# cpu.net
KiCad netlist of a schematic drawn in Altium Designer
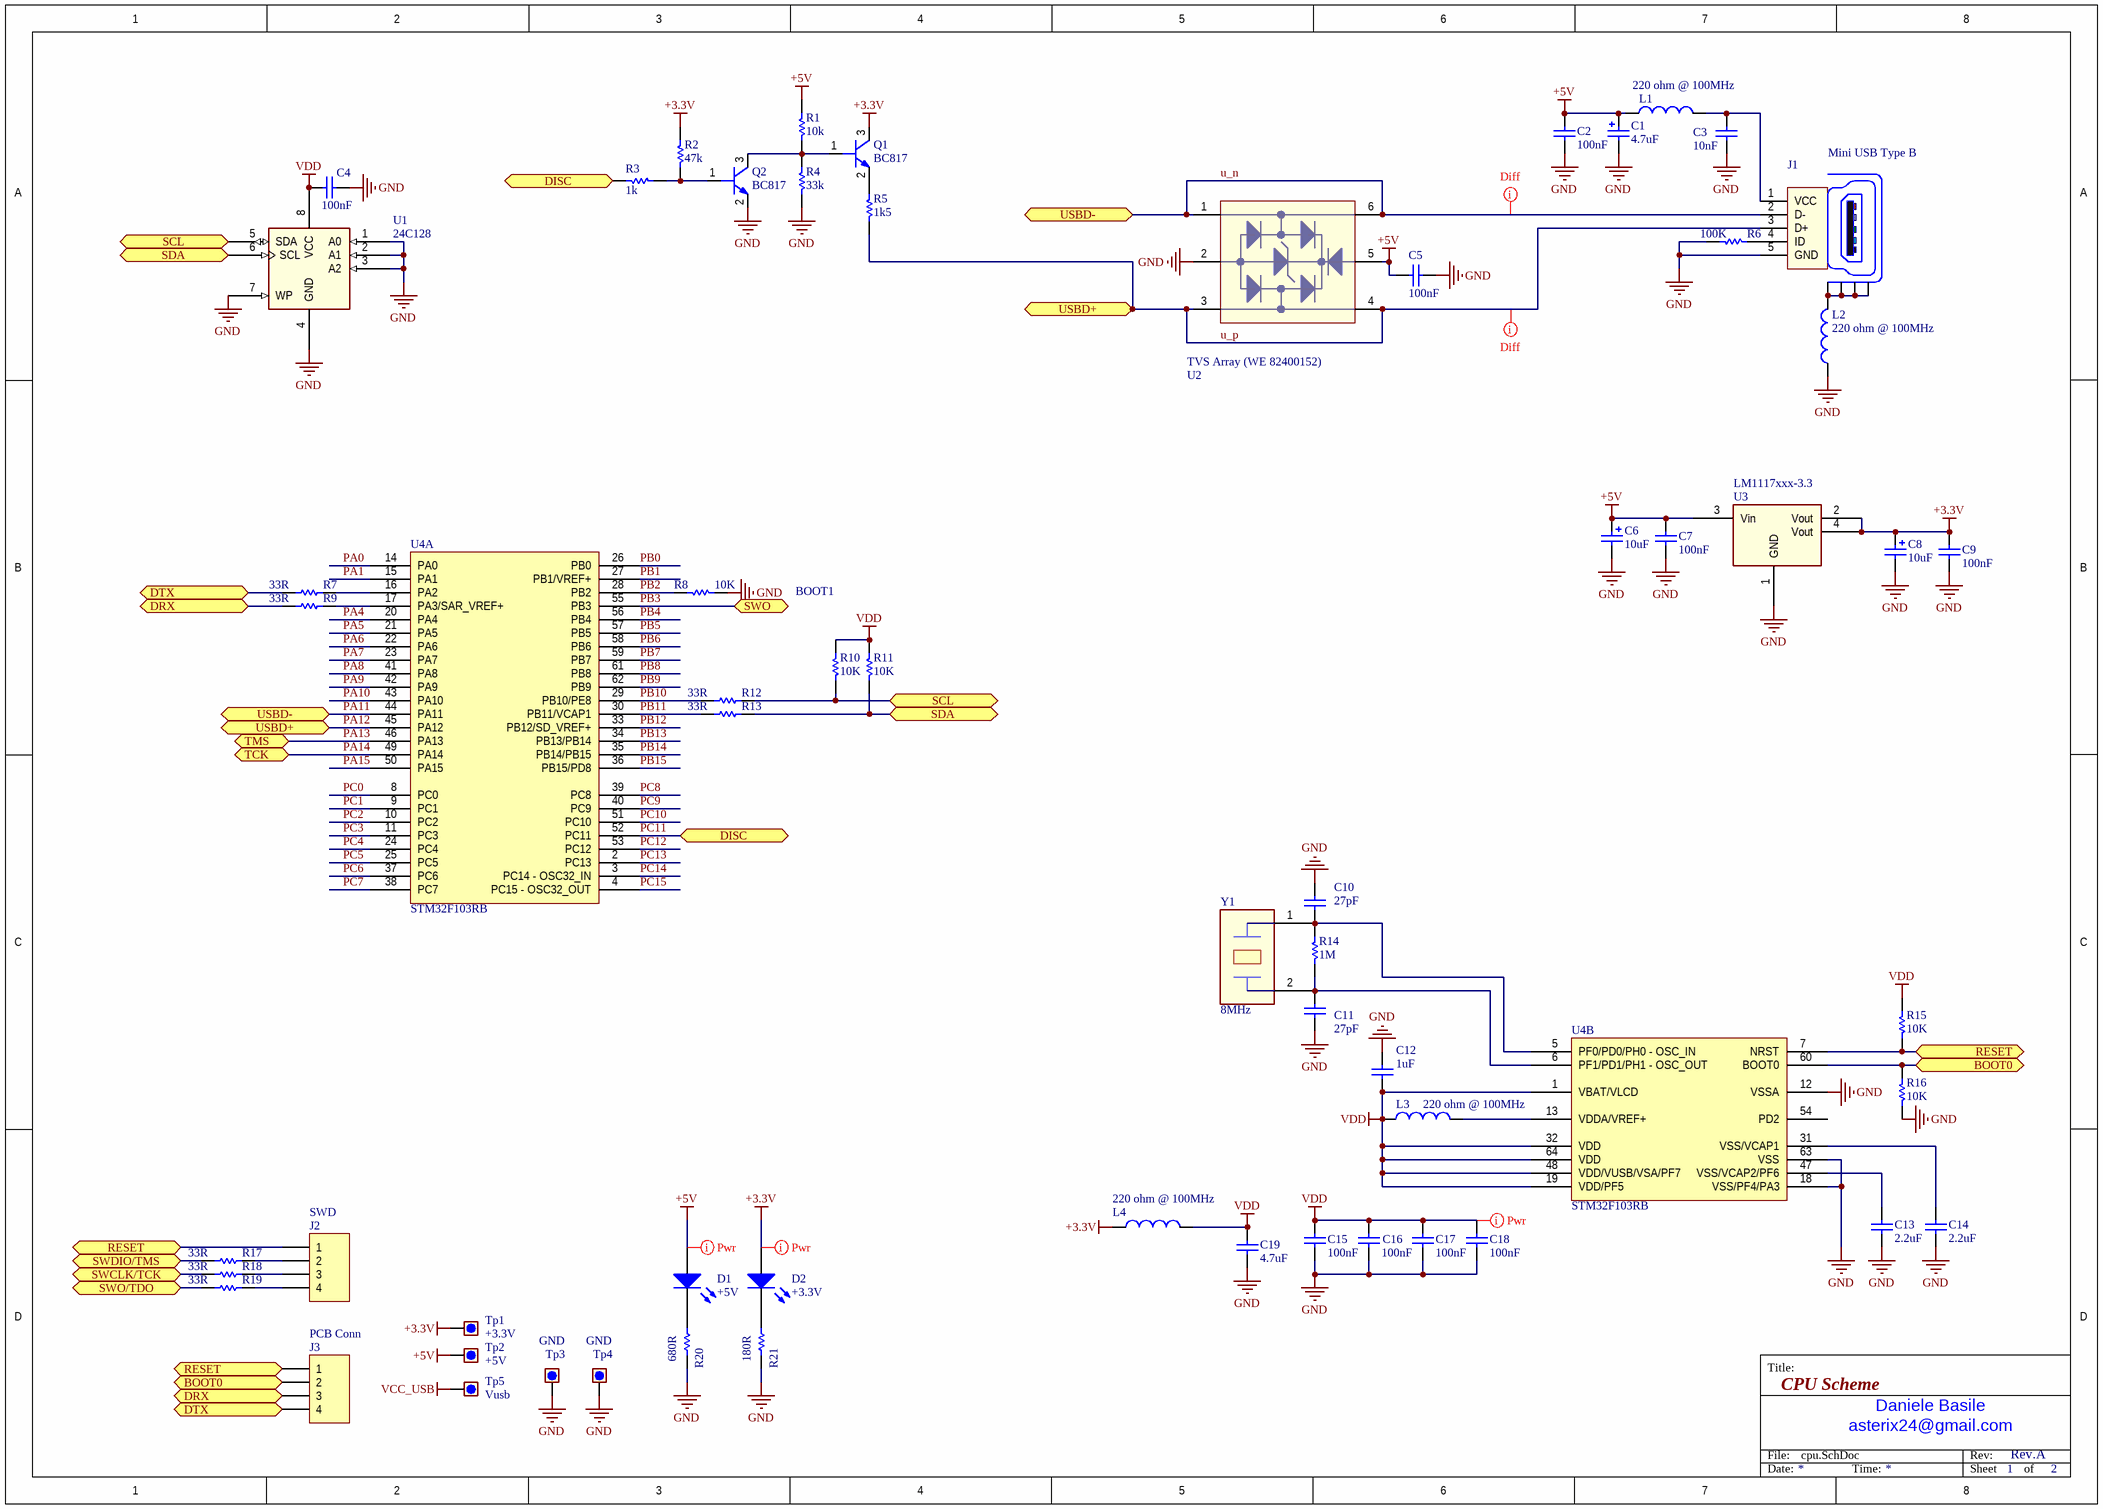
[diagram p0: cpu.SchDoc]

(export (version "E")
  (design (tool "Eeschema 10.0.6"))
  (components
    (comp (ref "C1")
      (value "4.7uF")
      (footprint "1206_[3216]")
      (description "Ceramic X7R 16V")
      (fields (field (name "PUBLISHER") "Altium Limited"))
      (libsource (lib "DEVELER_Library") (part "Cap Pol1"))
    )
    (comp (ref "C2")
      (value "100nF")
      (footprint "0603_[1608]")
      (description "Ceramic X7R 50V")
      (fields (field (name "PUBLISHER") "Altium Limited"))
      (libsource (lib "DEVELER_Library") (part "Cap"))
    )
    (comp (ref "C3")
      (value "10nF")
      (footprint "0603_[1608]")
      (description "Ceramic X7R 50V")
      (fields (field (name "PUBLISHER") "Altium Limited"))
      (libsource (lib "DEVELER_Library") (part "Cap"))
    )
    (comp (ref "C4")
      (value "100nF")
      (footprint "0603_[1608]")
      (description "Ceramic X7R 50V")
      (fields (field (name "PUBLISHER") "Altium Limited"))
      (libsource (lib "DEVELER_Library") (part "Cap"))
    )
    (comp (ref "C5")
      (value "100nF")
      (footprint "0603_[1608]")
      (description "Ceramic X7R 50V")
      (fields (field (name "PUBLISHER") "Altium Limited"))
      (libsource (lib "Miscellaneous Devices") (part "Cap"))
    )
    (comp (ref "C6")
      (value "10uF")
      (footprint "1206_[3216]")
      (description "Ceramic X5R 25V")
      (fields (field (name "PUBLISHER") "Altium Limited"))
      (libsource (lib "") (part "Cap Pol1_1"))
    )
    (comp (ref "C7")
      (value "100nF")
      (footprint "0603_[1608]")
      (description "Ceramic X7R 50V")
      (fields (field (name "PUBLISHER") "Altium Limited"))
      (libsource (lib "") (part "Cap_1"))
    )
    (comp (ref "C8")
      (value "10uF")
      (footprint "1206_[3216]")
      (description "Ceramic X5R 25V")
      (fields (field (name "PUBLISHER") "Altium Limited"))
      (libsource (lib "") (part "Cap Pol1_1"))
    )
    (comp (ref "C9")
      (value "100nF")
      (footprint "0603_[1608]")
      (description "Ceramic X7R 50V")
      (fields (field (name "PUBLISHER") "Altium Limited"))
      (libsource (lib "") (part "Cap_1"))
    )
    (comp (ref "C10")
      (value "27pF")
      (footprint "0603_[1608]")
      (description "Ceramic NP0 +/- 0.1")
      (fields (field (name "PUBLISHER") "Altium Limited"))
      (libsource (lib "simboli") (part "Cap"))
    )
    (comp (ref "C11")
      (value "27pF")
      (footprint "0603_[1608]")
      (description "Ceramic NP0 +/- 0.1")
      (fields (field (name "PUBLISHER") "Altium Limited"))
      (libsource (lib "simboli") (part "Cap"))
    )
    (comp (ref "C12")
      (value "1uF")
      (footprint "0603_[1608]")
      (description "Ceramic X7R 16V")
      (fields (field (name "PUBLISHER") "Altium Limited"))
      (libsource (lib "Miscellaneous Devices") (part "Cap"))
    )
    (comp (ref "C13")
      (value "2.2uF")
      (footprint "0603_[1608]")
      (description "Ceramic 6.3V X7R")
      (fields (field (name "PUBLISHER") "Altium Limited"))
      (libsource (lib "Miscellaneous Devices") (part "Cap"))
    )
    (comp (ref "C14")
      (value "2.2uF")
      (footprint "0603_[1608]")
      (description "Ceramic 6.3V X7R")
      (fields (field (name "PUBLISHER") "Altium Limited"))
      (libsource (lib "Miscellaneous Devices") (part "Cap"))
    )
    (comp (ref "C15")
      (value "100nF")
      (footprint "0603_[1608]")
      (description "Ceramic X7R 50V")
      (fields (field (name "PUBLISHER") "Altium Limited"))
      (libsource (lib "Miscellaneous Devices") (part "Cap"))
    )
    (comp (ref "C16")
      (value "100nF")
      (footprint "0603_[1608]")
      (description "Ceramic X7R 50V")
      (fields (field (name "PUBLISHER") "Altium Limited"))
      (libsource (lib "Miscellaneous Devices") (part "Cap"))
    )
    (comp (ref "C17")
      (value "100nF")
      (footprint "0603_[1608]")
      (description "Ceramic X7R 50V")
      (fields (field (name "PUBLISHER") "Altium Limited"))
      (libsource (lib "Miscellaneous Devices") (part "Cap"))
    )
    (comp (ref "C18")
      (value "100nF")
      (footprint "0603_[1608]")
      (description "Ceramic X7R 50V")
      (fields (field (name "PUBLISHER") "Altium Limited"))
      (libsource (lib "Miscellaneous Devices") (part "Cap"))
    )
    (comp (ref "C19")
      (value "4.7uF")
      (footprint "0603_[1608]")
      (description "Ceramic X7R 16V")
      (fields (field (name "PUBLISHER") "Altium Limited"))
      (libsource (lib "simboli") (part "Cap"))
    )
    (comp (ref "D1")
      (value "+5V")
      (footprint "0603_[1608]_LED")
      (description "LED Green")
      (fields (field (name "PUBLISHER") "Altium Limited"))
      (libsource (lib "DEVELER_Library") (part "LED0"))
    )
    (comp (ref "D2")
      (value "+3.3V")
      (footprint "0603_[1608]_LED")
      (description "LED Green")
      (fields (field (name "PUBLISHER") "Altium Limited"))
      (libsource (lib "DEVELER_Library") (part "LED0"))
    )
    (comp (ref "J1")
      (value "Mini USB Type B")
      (footprint "usb_typeB_mini_smd")
      (description "Mini USB SMT Type B 5 Contacts")
      (fields
        (field (name "MANUFACTURER") "Würth Elektronik eiSos GmbH")
        (field (name "PARTNO") "65100516121")
        (field (name "CREATED BY") "Karrer Zheng")
      )
      (libsource (lib "develer_library") (part "USB_Con_Type_B_mini_SMT"))
    )
    (comp (ref "J2")
      (value "SWD")
      (footprint "HEADER_1X4_2.54MM_THD")
      (description "Pin Header, 1x4, 2.54mm.")
      (fields (field (name "PUBLISHER") "Altium Limited"))
      (libsource (lib "Miscellaneous Connectors") (part "Header 4"))
    )
    (comp (ref "J3")
      (value "PCB Conn")
      (footprint "HEADER_1X4_2.54MM_THD")
      (description "Pin Header, 1x4, 2.54mm.")
      (fields (field (name "PUBLISHER") "Altium Limited"))
      (libsource (lib "Miscellaneous Connectors") (part "Header 4"))
    )
    (comp (ref "L1")
      (value "220 ohm @ 100MHz")
      (footprint "0805_[2012]")
      (description "WE 742792022")
      (libsource (lib "DEVELER_Library") (part "Inductor"))
    )
    (comp (ref "L2")
      (value "220 ohm @ 100MHz")
      (footprint "0805_[2012]")
      (description "WE 742792022")
      (libsource (lib "DEVELER_Library") (part "Inductor"))
    )
    (comp (ref "L3")
      (value "220 ohm @ 100MHz")
      (footprint "0805_[2012]")
      (description "Inductor")
      (fields (field (name "PUBLISHER") "Altium Limited"))
      (libsource (lib "Miscellaneous Devices") (part "Inductor"))
    )
    (comp (ref "L4")
      (value "220 ohm @ 100MHz")
      (footprint "0805_[2012]")
      (description "WE 742792022")
      (libsource (lib "DEVELER_Library") (part "Inductor"))
    )
    (comp (ref "Q1")
      (value "BC817")
      (footprint "SOT-23")
      (description "BJT NPN")
      (libsource (lib "develer_library") (part "BC817"))
    )
    (comp (ref "Q2")
      (value "BC817")
      (footprint "SOT-23")
      (description "BJT NPN")
      (libsource (lib "develer_library") (part "BC817"))
    )
    (comp (ref "R1")
      (value "10k")
      (footprint "0603_[1608]")
      (description "Resistor")
      (fields (field (name "PUBLISHER") "Altium Limited"))
      (libsource (lib "") (part "Res1_1"))
    )
    (comp (ref "R2")
      (value "47k")
      (footprint "0603_[1608]")
      (description "Resistor")
      (fields (field (name "PUBLISHER") "Altium Limited"))
      (libsource (lib "") (part "Res1_1"))
    )
    (comp (ref "R3")
      (value "1k")
      (footprint "0603_[1608]")
      (description "Resistor")
      (fields (field (name "PUBLISHER") "Altium Limited"))
      (libsource (lib "") (part "Res1_1"))
    )
    (comp (ref "R4")
      (value "33k")
      (footprint "0603_[1608]")
      (description "Resistor")
      (fields (field (name "PUBLISHER") "Altium Limited"))
      (libsource (lib "") (part "Res1_1"))
    )
    (comp (ref "R5")
      (value "1k5")
      (footprint "0603_[1608]")
      (description "Resistor")
      (fields (field (name "PUBLISHER") "Altium Limited"))
      (libsource (lib "") (part "Res1_1"))
    )
    (comp (ref "R6")
      (value "100K")
      (footprint "0603_[1608]")
      (description "Resistor")
      (libsource (lib "Miscellaneous Devices") (part "Res1"))
    )
    (comp (ref "R7")
      (value "33R")
      (footprint "0603_[1608]")
      (description "Resistor")
      (fields (field (name "PUBLISHER") "Altium Limited"))
      (libsource (lib "simboli") (part "Res1"))
    )
    (comp (ref "R8")
      (value "10K")
      (footprint "0603_[1608]")
      (description "Resistor")
      (fields (field (name "PUBLISHER") "Altium Limited"))
      (libsource (lib "simboli") (part "Res1"))
    )
    (comp (ref "R9")
      (value "33R")
      (footprint "0603_[1608]")
      (description "Resistor")
      (fields (field (name "PUBLISHER") "Altium Limited"))
      (libsource (lib "simboli") (part "Res1"))
    )
    (comp (ref "R10")
      (value "10K")
      (footprint "0603_[1608]")
      (description "Resistor")
      (fields (field (name "PUBLISHER") "Altium Limited"))
      (libsource (lib "") (part "Res1_1"))
    )
    (comp (ref "R11")
      (value "10K")
      (footprint "0603_[1608]")
      (description "Resistor")
      (fields (field (name "PUBLISHER") "Altium Limited"))
      (libsource (lib "") (part "Res1_1"))
    )
    (comp (ref "R12")
      (value "33R")
      (footprint "0603_[1608]")
      (description "Resistor")
      (fields (field (name "PUBLISHER") "Altium Limited"))
      (libsource (lib "simboli") (part "Res1"))
    )
    (comp (ref "R13")
      (value "33R")
      (footprint "0603_[1608]")
      (description "Resistor")
      (fields (field (name "PUBLISHER") "Altium Limited"))
      (libsource (lib "simboli") (part "Res1"))
    )
    (comp (ref "R14")
      (value "1M")
      (footprint "0603_[1608]")
      (description "Resistor")
      (fields (field (name "PUBLISHER") "Altium Limited"))
      (libsource (lib "") (part "Res1_1"))
    )
    (comp (ref "R15")
      (value "10K")
      (footprint "0603_[1608]")
      (description "Resistor")
      (fields (field (name "PUBLISHER") "Altium Limited"))
      (libsource (lib "simboli") (part "Res1"))
    )
    (comp (ref "R16")
      (value "10K")
      (footprint "0603_[1608]")
      (description "Resistor")
      (fields (field (name "PUBLISHER") "Altium Limited"))
      (libsource (lib "simboli") (part "Res1"))
    )
    (comp (ref "R17")
      (value "33R")
      (footprint "0603_[1608]")
      (description "Resistor")
      (fields (field (name "PUBLISHER") "Altium Limited"))
      (libsource (lib "simboli") (part "Res1"))
    )
    (comp (ref "R18")
      (value "33R")
      (footprint "0603_[1608]")
      (description "Resistor")
      (fields (field (name "PUBLISHER") "Altium Limited"))
      (libsource (lib "simboli") (part "Res1"))
    )
    (comp (ref "R19")
      (value "33R")
      (footprint "0603_[1608]")
      (description "Resistor")
      (fields (field (name "PUBLISHER") "Altium Limited"))
      (libsource (lib "simboli") (part "Res1"))
    )
    (comp (ref "R20")
      (value "680R")
      (footprint "0603_[1608]")
      (description "Resistor")
      (libsource (lib "DEVELER_Library") (part "Res1"))
    )
    (comp (ref "R21")
      (value "180R")
      (footprint "0603_[1608]")
      (description "Resistor")
      (libsource (lib "DEVELER_Library") (part "Res1"))
    )
    (comp (ref "Tp1")
      (value "+3.3V")
      (footprint "TEST_POINT_THD_D1.8MM")
      (description "Test point")
      (libsource (lib "DEVELER_Library") (part "Test_point"))
    )
    (comp (ref "Tp2")
      (value "+5V")
      (footprint "TEST_POINT_THD_D1.8MM")
      (description "Test point")
      (libsource (lib "DEVELER_Library") (part "Test_point"))
    )
    (comp (ref "Tp3")
      (value "GND")
      (footprint "TEST_POINT_THD_D1.8MM")
      (description "Test point")
      (libsource (lib "") (part "Test_point_1"))
    )
    (comp (ref "Tp4")
      (value "GND")
      (footprint "TEST_POINT_THD_D1.8MM")
      (description "Test point")
      (libsource (lib "") (part "Test_point_1"))
    )
    (comp (ref "Tp5")
      (value "Vusb")
      (footprint "TEST_POINT_THD_D1.8MM")
      (description "Test point")
      (libsource (lib "DEVELER_Library") (part "Test_point"))
    )
    (comp (ref "U1")
      (value "24C128")
      (footprint "SOIC8")
      (description "EEPROM")
      (libsource (lib "DEVELER_Library") (part "EEPROM-SOIC8"))
    )
    (comp (ref "U2")
      (value "TVS Array (WE 82400152)")
      (footprint "SOT-563")
      (libsource (lib "DEVELER_Library") (part "TVS_Diode_Array"))
    )
    (comp (ref "U3")
      (value "LM1117xxx-3.3")
      (footprint "SOT-223")
      (description "LM1117 LDO Fixed output")
      (libsource (lib "develer_library") (part "LM1117-FIXED-OUT"))
    )
    (comp (ref "U4")
      (value "STM32F103RB")
      (footprint "TSQFP50P1200X1200X160-64N")
      (libsource (lib "develer_library") (part "STM32F103RB"))
    )
    (comp (ref "Y1")
      (value "8MHz")
      (footprint "CRYSTAL_HC49UP")
      (libsource (lib "develer_library") (part "CRYSTAL-2p"))
    )
  )
  (nets
    (net (code "1") (name "+3.3V") (class "Default")
      (node (ref "C8") (pin "1") (pinfunction "1_1") (pintype "passive"))
      (node (ref "C9") (pin "2") (pinfunction "2_2") (pintype "passive"))
      (node (ref "D2") (pin "1") (pinfunction "A_1") (pintype "passive"))
      (node (ref "L4") (pin "1") (pinfunction "1_1") (pintype "passive"))
      (node (ref "Q1") (pin "3") (pinfunction "C_3") (pintype "passive"))
      (node (ref "R2") (pin "1") (pinfunction "1_1") (pintype "passive"))
      (node (ref "Tp1") (pin "1") (pinfunction "1_1") (pintype "passive"))
      (node (ref "U3") (pin "2") (pinfunction "Vout_2") (pintype "passive"))
      (node (ref "U3") (pin "4") (pinfunction "Vout_4") (pintype "passive"))
    )
    (net (code "2") (name "+5V") (class "Default")
      (node (ref "C1") (pin "1") (pinfunction "1_1") (pintype "passive"))
      (node (ref "C2") (pin "1") (pinfunction "1_1") (pintype "passive"))
      (node (ref "C5") (pin "2") (pinfunction "2_2") (pintype "passive"))
      (node (ref "C6") (pin "1") (pinfunction "1_1") (pintype "passive"))
      (node (ref "C7") (pin "2") (pinfunction "2_2") (pintype "passive"))
      (node (ref "D1") (pin "1") (pinfunction "A_1") (pintype "passive"))
      (node (ref "L1") (pin "1") (pinfunction "1_1") (pintype "passive"))
      (node (ref "R1") (pin "1") (pinfunction "1_1") (pintype "passive"))
      (node (ref "Tp2") (pin "1") (pinfunction "1_1") (pintype "passive"))
      (node (ref "U2") (pin "5") (pinfunction "5_5") (pintype "passive"))
      (node (ref "U3") (pin "3") (pinfunction "Vin_3") (pintype "passive"))
    )
    (net (code "3") (name "/BOOT0") (class "Default")
      (node (ref "J3") (pin "2") (pinfunction "2_2") (pintype "passive"))
      (node (ref "R16") (pin "2") (pinfunction "2_2") (pintype "passive"))
      (node (ref "U4") (pin "60") (pinfunction "BOOT0_60") (pintype "passive"))
    )
    (net (code "4") (name "/DRX") (class "Default")
      (node (ref "J3") (pin "3") (pinfunction "3_3") (pintype "passive"))
      (node (ref "R9") (pin "2") (pinfunction "2_2") (pintype "passive"))
    )
    (net (code "5") (name "/DTX") (class "Default")
      (node (ref "J3") (pin "4") (pinfunction "4_4") (pintype "passive"))
      (node (ref "R7") (pin "2") (pinfunction "2_2") (pintype "passive"))
    )
    (net (code "6") (name "/PA0") (class "Default")
      (node (ref "U4") (pin "14") (pinfunction "PA0_14") (pintype "passive"))
    )
    (net (code "7") (name "/PA1") (class "Default")
      (node (ref "U4") (pin "15") (pinfunction "PA1_15") (pintype "passive"))
    )
    (net (code "8") (name "/PA4") (class "Default")
      (node (ref "U4") (pin "20") (pinfunction "PA4_20") (pintype "passive"))
    )
    (net (code "9") (name "/PA5") (class "Default")
      (node (ref "U4") (pin "21") (pinfunction "PA5_21") (pintype "passive"))
    )
    (net (code "10") (name "/PA6") (class "Default")
      (node (ref "U4") (pin "22") (pinfunction "PA6_22") (pintype "passive"))
    )
    (net (code "11") (name "/PA7") (class "Default")
      (node (ref "U4") (pin "23") (pinfunction "PA7_23") (pintype "passive"))
    )
    (net (code "12") (name "/PA8") (class "Default")
      (node (ref "U4") (pin "41") (pinfunction "PA8_41") (pintype "passive"))
    )
    (net (code "13") (name "/PA9") (class "Default")
      (node (ref "U4") (pin "42") (pinfunction "PA9_42") (pintype "passive"))
    )
    (net (code "14") (name "/PA10") (class "Default")
      (node (ref "U4") (pin "43") (pinfunction "PA10_43") (pintype "passive"))
    )
    (net (code "15") (name "/PA11") (class "Default")
      (node (ref "J1") (pin "2") (pinfunction "D-_2") (pintype "passive"))
      (node (ref "U2") (pin "1") (pinfunction "1_1") (pintype "passive"))
      (node (ref "U2") (pin "6") (pinfunction "6_6") (pintype "passive"))
      (node (ref "U4") (pin "44") (pinfunction "PA11_44") (pintype "passive"))
    )
    (net (code "16") (name "/PA12") (class "Default")
      (node (ref "J1") (pin "3") (pinfunction "D+_3") (pintype "passive"))
      (node (ref "R5") (pin "2") (pinfunction "2_2") (pintype "passive"))
      (node (ref "U2") (pin "3") (pinfunction "3_3") (pintype "passive"))
      (node (ref "U2") (pin "4") (pinfunction "4_4") (pintype "passive"))
      (node (ref "U4") (pin "45") (pinfunction "PA12_45") (pintype "passive"))
    )
    (net (code "17") (name "/PA13") (class "Default")
      (node (ref "U4") (pin "46") (pinfunction "PA13_46") (pintype "passive"))
    )
    (net (code "18") (name "/PA14") (class "Default")
      (node (ref "U4") (pin "49") (pinfunction "PA14_49") (pintype "passive"))
    )
    (net (code "19") (name "/PA15") (class "Default")
      (node (ref "U4") (pin "50") (pinfunction "PA15_50") (pintype "passive"))
    )
    (net (code "20") (name "/PB0") (class "Default")
      (node (ref "U4") (pin "26") (pinfunction "PB0_26") (pintype "passive"))
    )
    (net (code "21") (name "/PB1") (class "Default")
      (node (ref "U4") (pin "27") (pinfunction "PB1/VREF+_27") (pintype "passive"))
    )
    (net (code "22") (name "/PB2") (class "Default")
      (node (ref "R8") (pin "1") (pinfunction "1_1") (pintype "passive"))
      (node (ref "U4") (pin "28") (pinfunction "PB2_28") (pintype "passive"))
    )
    (net (code "23") (name "/PB3") (class "Default")
      (node (ref "U4") (pin "55") (pinfunction "PB3_55") (pintype "passive"))
    )
    (net (code "24") (name "/PB4") (class "Default")
      (node (ref "U4") (pin "56") (pinfunction "PB4_56") (pintype "passive"))
    )
    (net (code "25") (name "/PB5") (class "Default")
      (node (ref "U4") (pin "57") (pinfunction "PB5_57") (pintype "passive"))
    )
    (net (code "26") (name "/PB6") (class "Default")
      (node (ref "U4") (pin "58") (pinfunction "PB6_58") (pintype "passive"))
    )
    (net (code "27") (name "/PB7") (class "Default")
      (node (ref "U4") (pin "59") (pinfunction "PB7_59") (pintype "passive"))
    )
    (net (code "28") (name "/PB8") (class "Default")
      (node (ref "U4") (pin "61") (pinfunction "PB8_61") (pintype "passive"))
    )
    (net (code "29") (name "/PB9") (class "Default")
      (node (ref "U4") (pin "62") (pinfunction "PB9_62") (pintype "passive"))
    )
    (net (code "30") (name "/PB10") (class "Default")
      (node (ref "R12") (pin "2") (pinfunction "2_2") (pintype "passive"))
      (node (ref "U4") (pin "29") (pinfunction "PB10/PE8_29") (pintype "passive"))
    )
    (net (code "31") (name "/PB11") (class "Default")
      (node (ref "R13") (pin "2") (pinfunction "2_2") (pintype "passive"))
      (node (ref "U4") (pin "30") (pinfunction "PB11/VCAP1_30") (pintype "passive"))
    )
    (net (code "32") (name "/PB12") (class "Default")
      (node (ref "U4") (pin "33") (pinfunction "PB12/SD_VREF+_33") (pintype "passive"))
    )
    (net (code "33") (name "/PB13") (class "Default")
      (node (ref "U4") (pin "34") (pinfunction "PB13/PB14_34") (pintype "passive"))
    )
    (net (code "34") (name "/PB14") (class "Default")
      (node (ref "U4") (pin "35") (pinfunction "PB14/PB15_35") (pintype "passive"))
    )
    (net (code "35") (name "/PB15") (class "Default")
      (node (ref "U4") (pin "36") (pinfunction "PB15/PD8_36") (pintype "passive"))
    )
    (net (code "36") (name "/PC0") (class "Default")
      (node (ref "U4") (pin "8") (pinfunction "PC0_8") (pintype "passive"))
    )
    (net (code "37") (name "/PC1") (class "Default")
      (node (ref "U4") (pin "9") (pinfunction "PC1_9") (pintype "passive"))
    )
    (net (code "38") (name "/PC2") (class "Default")
      (node (ref "U4") (pin "10") (pinfunction "PC2_10") (pintype "passive"))
    )
    (net (code "39") (name "/PC3") (class "Default")
      (node (ref "U4") (pin "11") (pinfunction "PC3_11") (pintype "passive"))
    )
    (net (code "40") (name "/PC4") (class "Default")
      (node (ref "U4") (pin "24") (pinfunction "PC4_24") (pintype "passive"))
    )
    (net (code "41") (name "/PC5") (class "Default")
      (node (ref "U4") (pin "25") (pinfunction "PC5_25") (pintype "passive"))
    )
    (net (code "42") (name "/PC6") (class "Default")
      (node (ref "U4") (pin "37") (pinfunction "PC6_37") (pintype "passive"))
    )
    (net (code "43") (name "/PC7") (class "Default")
      (node (ref "U4") (pin "38") (pinfunction "PC7_38") (pintype "passive"))
    )
    (net (code "44") (name "/PC8") (class "Default")
      (node (ref "U4") (pin "39") (pinfunction "PC8_39") (pintype "passive"))
    )
    (net (code "45") (name "/PC9") (class "Default")
      (node (ref "U4") (pin "40") (pinfunction "PC9_40") (pintype "passive"))
    )
    (net (code "46") (name "/PC10") (class "Default")
      (node (ref "U4") (pin "51") (pinfunction "PC10_51") (pintype "passive"))
    )
    (net (code "47") (name "/PC11") (class "Default")
      (node (ref "R3") (pin "2") (pinfunction "2_2") (pintype "passive"))
      (node (ref "U4") (pin "52") (pinfunction "PC11_52") (pintype "passive"))
    )
    (net (code "48") (name "/PC12") (class "Default")
      (node (ref "U4") (pin "53") (pinfunction "PC12_53") (pintype "passive"))
    )
    (net (code "49") (name "/PC13") (class "Default")
      (node (ref "U4") (pin "2") (pinfunction "PC13_2") (pintype "passive"))
    )
    (net (code "50") (name "/PC14") (class "Default")
      (node (ref "U4") (pin "3") (pinfunction "PC14_-_OSC32_IN_3") (pintype "passive"))
    )
    (net (code "51") (name "/PC15") (class "Default")
      (node (ref "U4") (pin "4") (pinfunction "PC15_-_OSC32_OUT_4") (pintype "passive"))
    )
    (net (code "52") (name "/RESET") (class "Default")
      (node (ref "J2") (pin "1") (pinfunction "1_1") (pintype "passive"))
      (node (ref "J3") (pin "1") (pinfunction "1_1") (pintype "passive"))
      (node (ref "R15") (pin "2") (pinfunction "2_2") (pintype "passive"))
      (node (ref "U4") (pin "7") (pinfunction "NRST_7") (pintype "passive"))
    )
    (net (code "53") (name "/SCL") (class "Default")
      (node (ref "R10") (pin "1") (pinfunction "1_1") (pintype "passive"))
      (node (ref "R12") (pin "1") (pinfunction "1_1") (pintype "passive"))
      (node (ref "U1") (pin "5") (pinfunction "SDA_5") (pintype "bidirectional"))
    )
    (net (code "54") (name "/SDA") (class "Default")
      (node (ref "R11") (pin "1") (pinfunction "1_1") (pintype "passive"))
      (node (ref "R13") (pin "1") (pinfunction "1_1") (pintype "passive"))
      (node (ref "U1") (pin "6") (pinfunction "SCL_6") (pintype "input"))
    )
    (net (code "55") (name "/SWCLK{slash}TCK") (class "Default")
      (node (ref "R18") (pin "2") (pinfunction "2_2") (pintype "passive"))
    )
    (net (code "56") (name "/SWDIO{slash}TMS") (class "Default")
      (node (ref "R17") (pin "2") (pinfunction "2_2") (pintype "passive"))
    )
    (net (code "57") (name "/SWO{slash}TDO") (class "Default")
      (node (ref "R19") (pin "2") (pinfunction "2_2") (pintype "passive"))
    )
    (net (code "58") (name "GND") (class "Default")
      (node (ref "C1") (pin "2") (pinfunction "2_2") (pintype "passive"))
      (node (ref "C10") (pin "2") (pinfunction "2_2") (pintype "passive"))
      (node (ref "C11") (pin "2") (pinfunction "2_2") (pintype "passive"))
      (node (ref "C12") (pin "2") (pinfunction "2_2") (pintype "passive"))
      (node (ref "C13") (pin "1") (pinfunction "1_1") (pintype "passive"))
      (node (ref "C14") (pin "1") (pinfunction "1_1") (pintype "passive"))
      (node (ref "C15") (pin "2") (pinfunction "2_2") (pintype "passive"))
      (node (ref "C16") (pin "2") (pinfunction "2_2") (pintype "passive"))
      (node (ref "C17") (pin "2") (pinfunction "2_2") (pintype "passive"))
      (node (ref "C18") (pin "2") (pinfunction "2_2") (pintype "passive"))
      (node (ref "C19") (pin "1") (pinfunction "1_1") (pintype "passive"))
      (node (ref "C2") (pin "2") (pinfunction "2_2") (pintype "passive"))
      (node (ref "C3") (pin "2") (pinfunction "2_2") (pintype "passive"))
      (node (ref "C4") (pin "1") (pinfunction "1_1") (pintype "passive"))
      (node (ref "C5") (pin "1") (pinfunction "1_1") (pintype "passive"))
      (node (ref "C6") (pin "2") (pinfunction "2_2") (pintype "passive"))
      (node (ref "C7") (pin "1") (pinfunction "1_1") (pintype "passive"))
      (node (ref "C8") (pin "2") (pinfunction "2_2") (pintype "passive"))
      (node (ref "C9") (pin "1") (pinfunction "1_1") (pintype "passive"))
      (node (ref "J1") (pin "5") (pinfunction "GND_5") (pintype "passive"))
      (node (ref "L2") (pin "1") (pinfunction "1_1") (pintype "passive"))
      (node (ref "Q2") (pin "2") (pinfunction "E_2") (pintype "passive"))
      (node (ref "R16") (pin "1") (pinfunction "1_1") (pintype "passive"))
      (node (ref "R20") (pin "1") (pinfunction "1_1") (pintype "passive"))
      (node (ref "R21") (pin "1") (pinfunction "1_1") (pintype "passive"))
      (node (ref "R4") (pin "2") (pinfunction "2_2") (pintype "passive"))
      (node (ref "R6") (pin "2") (pinfunction "2_2") (pintype "passive"))
      (node (ref "R8") (pin "2") (pinfunction "2_2") (pintype "passive"))
      (node (ref "Tp3") (pin "1") (pinfunction "1_1") (pintype "passive"))
      (node (ref "Tp4") (pin "1") (pinfunction "1_1") (pintype "passive"))
      (node (ref "U1") (pin "1") (pinfunction "A0_1") (pintype "input"))
      (node (ref "U1") (pin "2") (pinfunction "A1_2") (pintype "input"))
      (node (ref "U1") (pin "3") (pinfunction "A2_3") (pintype "input"))
      (node (ref "U1") (pin "4") (pinfunction "GND_4") (pintype "power_in"))
      (node (ref "U1") (pin "7") (pinfunction "WP_7") (pintype "input"))
      (node (ref "U2") (pin "2") (pinfunction "2_2") (pintype "passive"))
      (node (ref "U3") (pin "1") (pinfunction "GND_1") (pintype "passive"))
      (node (ref "U4") (pin "12") (pinfunction "VSSA_12") (pintype "passive"))
      (node (ref "U4") (pin "18") (pinfunction "VSS/PF4/PA3_18") (pintype "passive"))
      (node (ref "U4") (pin "63") (pinfunction "VSS_63") (pintype "passive"))
    )
    (net (code "59") (name "Net-(D1-K)") (class "Default")
      (node (ref "D1") (pin "2") (pinfunction "K_2") (pintype "passive"))
      (node (ref "R20") (pin "2") (pinfunction "2_2") (pintype "passive"))
    )
    (net (code "60") (name "Net-(D2-K)") (class "Default")
      (node (ref "D2") (pin "2") (pinfunction "K_2") (pintype "passive"))
      (node (ref "R21") (pin "2") (pinfunction "2_2") (pintype "passive"))
    )
    (net (code "61") (name "Net-(J1-ID)") (class "Default")
      (node (ref "J1") (pin "4") (pinfunction "ID_4") (pintype "passive"))
      (node (ref "R6") (pin "1") (pinfunction "1_1") (pintype "passive"))
    )
    (net (code "62") (name "Net-(J1-Shield-PadZ1)") (class "Default")
      (node (ref "J1") (pin "Z1") (pinfunction "Shield_Z1") (pintype "passive"))
      (node (ref "J1") (pin "Z2") (pinfunction "Shield_Z2") (pintype "passive"))
      (node (ref "J1") (pin "Z3") (pinfunction "Shield_Z3") (pintype "passive"))
      (node (ref "J1") (pin "Z4") (pinfunction "Shield_Z4") (pintype "passive"))
      (node (ref "L2") (pin "2") (pinfunction "2_2") (pintype "passive"))
    )
    (net (code "63") (name "Net-(J1-VCC)") (class "Default")
      (node (ref "C3") (pin "1") (pinfunction "1_1") (pintype "passive"))
      (node (ref "J1") (pin "1") (pinfunction "VCC_1") (pintype "passive"))
      (node (ref "L1") (pin "2") (pinfunction "2_2") (pintype "passive"))
    )
    (net (code "64") (name "Net-(J2-Pad2)") (class "Default")
      (node (ref "J2") (pin "2") (pinfunction "2_2") (pintype "passive"))
      (node (ref "R17") (pin "1") (pinfunction "1_1") (pintype "passive"))
    )
    (net (code "65") (name "Net-(J2-Pad3)") (class "Default")
      (node (ref "J2") (pin "3") (pinfunction "3_3") (pintype "passive"))
      (node (ref "R18") (pin "1") (pinfunction "1_1") (pintype "passive"))
    )
    (net (code "66") (name "Net-(J2-Pad4)") (class "Default")
      (node (ref "J2") (pin "4") (pinfunction "4_4") (pintype "passive"))
      (node (ref "R19") (pin "1") (pinfunction "1_1") (pintype "passive"))
    )
    (net (code "67") (name "Net-(Q1-B)") (class "Default")
      (node (ref "Q1") (pin "1") (pinfunction "B_1") (pintype "passive"))
      (node (ref "Q2") (pin "3") (pinfunction "C_3") (pintype "passive"))
      (node (ref "R1") (pin "2") (pinfunction "2_2") (pintype "passive"))
      (node (ref "R4") (pin "1") (pinfunction "1_1") (pintype "passive"))
    )
    (net (code "68") (name "Net-(Q1-E)") (class "Default")
      (node (ref "Q1") (pin "2") (pinfunction "E_2") (pintype "passive"))
      (node (ref "R5") (pin "1") (pinfunction "1_1") (pintype "passive"))
    )
    (net (code "69") (name "Net-(Q2-B)") (class "Default")
      (node (ref "Q2") (pin "1") (pinfunction "B_1") (pintype "passive"))
      (node (ref "R2") (pin "2") (pinfunction "2_2") (pintype "passive"))
      (node (ref "R3") (pin "1") (pinfunction "1_1") (pintype "passive"))
    )
    (net (code "70") (name "Net-(U4A-PA2)") (class "Default")
      (node (ref "R7") (pin "1") (pinfunction "1_1") (pintype "passive"))
      (node (ref "U4") (pin "16") (pinfunction "PA2_16") (pintype "passive"))
    )
    (net (code "71") (name "Net-(U4A-PA3{slash}SAR_VREF+)") (class "Default")
      (node (ref "R9") (pin "1") (pinfunction "1_1") (pintype "passive"))
      (node (ref "U4") (pin "17") (pinfunction "PA3/SAR_VREF+_17") (pintype "passive"))
    )
    (net (code "72") (name "Net-(U4B-PF0{slash}PD0{slash}PH0_-_OSC_IN)") (class "Default")
      (node (ref "C10") (pin "1") (pinfunction "1_1") (pintype "passive"))
      (node (ref "R14") (pin "2") (pinfunction "2_2") (pintype "passive"))
      (node (ref "U4") (pin "5") (pinfunction "PF0/PD0/PH0_-_OSC_IN_5") (pintype "passive"))
      (node (ref "Y1") (pin "1") (pinfunction "1_1") (pintype "passive"))
    )
    (net (code "73") (name "Net-(U4B-PF1{slash}PD1{slash}PH1_-_OSC_OUT)") (class "Default")
      (node (ref "C11") (pin "1") (pinfunction "1_1") (pintype "passive"))
      (node (ref "R14") (pin "1") (pinfunction "1_1") (pintype "passive"))
      (node (ref "U4") (pin "6") (pinfunction "PF1/PD1/PH1_-_OSC_OUT_6") (pintype "passive"))
      (node (ref "Y1") (pin "2") (pinfunction "2_2") (pintype "passive"))
    )
    (net (code "74") (name "Net-(U4B-VDDA{slash}VREF+)") (class "Default")
      (node (ref "L3") (pin "2") (pinfunction "2_2") (pintype "passive"))
      (node (ref "U4") (pin "13") (pinfunction "VDDA/VREF+_13") (pintype "passive"))
    )
    (net (code "75") (name "Net-(U4B-VSS{slash}VCAP1)") (class "Default")
      (node (ref "C14") (pin "2") (pinfunction "2_2") (pintype "passive"))
      (node (ref "U4") (pin "31") (pinfunction "VSS/VCAP1_31") (pintype "passive"))
    )
    (net (code "76") (name "Net-(U4B-VSS{slash}VCAP2{slash}PF6)") (class "Default")
      (node (ref "C13") (pin "2") (pinfunction "2_2") (pintype "passive"))
      (node (ref "U4") (pin "47") (pinfunction "VSS/VCAP2/PF6_47") (pintype "passive"))
    )
    (net (code "77") (name "VCC_USB") (class "Default")
      (node (ref "Tp5") (pin "1") (pinfunction "1_1") (pintype "passive"))
    )
    (net (code "78") (name "VDD") (class "Default")
      (node (ref "C12") (pin "1") (pinfunction "1_1") (pintype "passive"))
      (node (ref "C15") (pin "1") (pinfunction "1_1") (pintype "passive"))
      (node (ref "C16") (pin "1") (pinfunction "1_1") (pintype "passive"))
      (node (ref "C17") (pin "1") (pinfunction "1_1") (pintype "passive"))
      (node (ref "C18") (pin "1") (pinfunction "1_1") (pintype "passive"))
      (node (ref "C19") (pin "2") (pinfunction "2_2") (pintype "passive"))
      (node (ref "C4") (pin "2") (pinfunction "2_2") (pintype "passive"))
      (node (ref "L3") (pin "1") (pinfunction "1_1") (pintype "passive"))
      (node (ref "L4") (pin "2") (pinfunction "2_2") (pintype "passive"))
      (node (ref "R10") (pin "2") (pinfunction "2_2") (pintype "passive"))
      (node (ref "R11") (pin "2") (pinfunction "2_2") (pintype "passive"))
      (node (ref "R15") (pin "1") (pinfunction "1_1") (pintype "passive"))
      (node (ref "U1") (pin "8") (pinfunction "VCC_8") (pintype "power_in"))
      (node (ref "U4") (pin "1") (pinfunction "VBAT/VLCD_1") (pintype "passive"))
      (node (ref "U4") (pin "19") (pinfunction "VDD/PF5_19") (pintype "passive"))
      (node (ref "U4") (pin "32") (pinfunction "VDD_32") (pintype "passive"))
      (node (ref "U4") (pin "48") (pinfunction "VDD/VUSB/VSA/PF7_48") (pintype "passive"))
      (node (ref "U4") (pin "64") (pinfunction "VDD_64") (pintype "passive"))
    )
    (net (code "79") (name "unconnected-(U4B-PD2-Pad54)") (class "Default")
      (node (ref "U4") (pin "54") (pinfunction "PD2_54") (pintype "passive"))
    )
  )
)
